# eBox_Power.net
KiCad netlist of a schematic drawn in Altium Designer
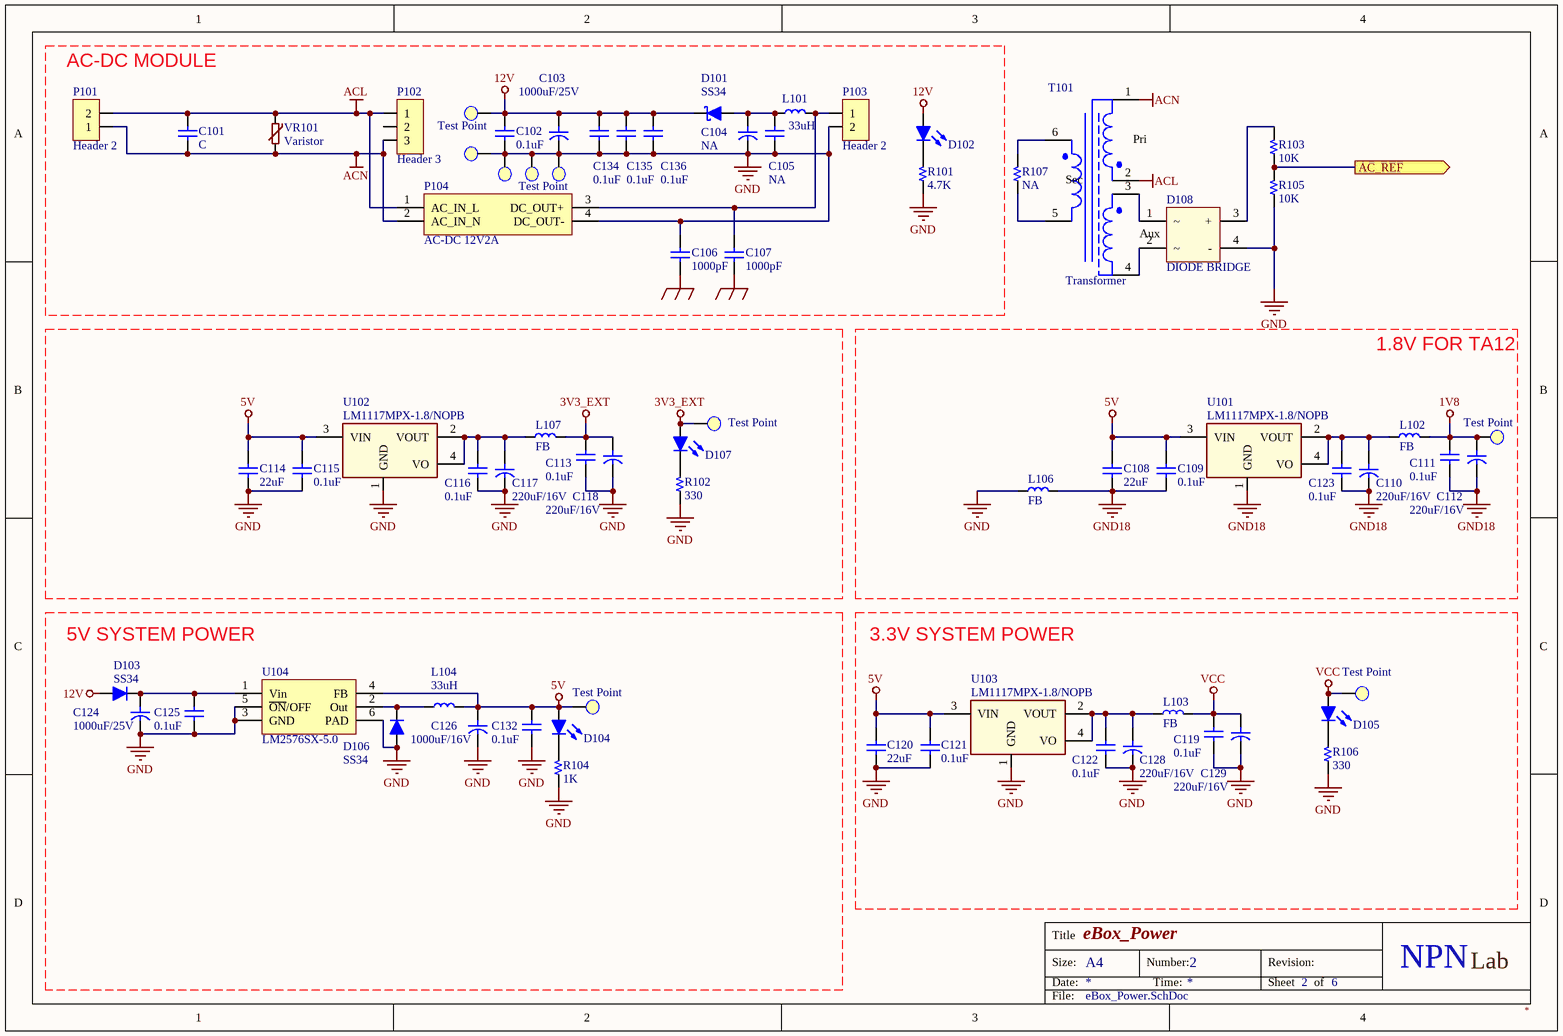
[diagram p0: eBox_Power.SchDoc]

(export (version "E")
  (design (tool "Eeschema 10.0.6"))
  (components
    (comp (ref "1V8")
      (value "Test Point")
      (footprint "TestPoint/SMD/1.5mm")
      (libsource (lib "chipfc_altium_libs_extras") (part "Test Point"))
    )
    (comp (ref "3V3")
      (value "Test Point")
      (footprint "TestPoint/SMD/1.5mm")
      (libsource (lib "chipfc_altium_libs_extras") (part "Test Point"))
    )
    (comp (ref "5V")
      (value "Test Point")
      (footprint "TestPoint/SMD/1.5mm")
      (libsource (lib "chipfc_altium_libs_extras") (part "Test Point"))
    )
    (comp (ref "12V")
      (value "Test Point")
      (footprint "TestPoint/SMD/1.5mm")
      (libsource (lib "chipfc_altium_libs_extras") (part "Test Point"))
    )
    (comp (ref "C101")
      (value "C")
      (footprint "CAP Ceramic/D7.0/F7.5")
      (description "Capacitor non-pol")
      (libsource (lib "chipfc_altium_libs") (part "Capacitor NP"))
    )
    (comp (ref "C102")
      (value "0.1uF")
      (footprint "C 0805")
      (description "CAP CER 0.1UF 50V X7R 0603")
      (libsource (lib "chipfc_altium_libs") (part "Capacitor NP"))
    )
    (comp (ref "C103")
      (value "1000uF/25V")
      (footprint "CAP/D100/H200/LS50")
      (description "Capacitor pol")
      (libsource (lib "") (part "Capacitor_1"))
    )
    (comp (ref "C104")
      (value "NA")
      (footprint "CAP/D100/H200/LS50")
      (description "Capacitor pol")
      (libsource (lib "") (part "Capacitor_1"))
    )
    (comp (ref "C105")
      (value "NA")
      (footprint "C 0805")
      (description "CAP CER 0.1UF 50V X7R 0805")
      (libsource (lib "chipfc_altium_libs") (part "Capacitor NP"))
    )
    (comp (ref "C106")
      (value "1000pF")
      (footprint "CAP Ceramic/W300")
      (description "Capacitor non-pol")
      (libsource (lib "chipfc_altium_libs") (part "Capacitor NP"))
    )
    (comp (ref "C107")
      (value "1000pF")
      (footprint "CAP Ceramic/W300")
      (description "Capacitor non-pol")
      (libsource (lib "chipfc_altium_libs") (part "Capacitor NP"))
    )
    (comp (ref "C108")
      (value "22uF")
      (footprint "C 1210")
      (description "CAP CER 22UF 50V X7R 1210")
      (libsource (lib "chipfc_altium_libs") (part "Capacitor NP"))
    )
    (comp (ref "C109")
      (value "0.1uF")
      (footprint "C 0805")
      (description "CAP CER 0.1UF 50V X7R 0603")
      (libsource (lib "chipfc_altium_libs") (part "Capacitor NP"))
    )
    (comp (ref "C110")
      (value "220uF/16V")
      (footprint "CYL/D.250/LS.100")
      (description "CAP TANT 100UF 20% 16V 2917")
      (libsource (lib "chipfc_altium_libs") (part "Capacitor"))
    )
    (comp (ref "C111")
      (value "0.1uF")
      (footprint "C 0805")
      (description "CAP CER 0.1UF 50V X7R 0603")
      (libsource (lib "chipfc_altium_libs") (part "Capacitor NP"))
    )
    (comp (ref "C112")
      (value "220uF/16V")
      (footprint "CYL/D.250/LS.100")
      (description "CAP TANT 100UF 20% 16V 2917")
      (libsource (lib "chipfc_altium_libs") (part "Capacitor"))
    )
    (comp (ref "C113")
      (value "0.1uF")
      (footprint "C 0805")
      (description "CAP CER 0.1UF 50V X7R 0603")
      (libsource (lib "chipfc_altium_libs") (part "Capacitor NP"))
    )
    (comp (ref "C114")
      (value "22uF")
      (footprint "C 1210")
      (description "CAP CER 22UF 50V X7R 1210")
      (libsource (lib "chipfc_altium_libs") (part "Capacitor NP"))
    )
    (comp (ref "C115")
      (value "0.1uF")
      (footprint "C 0805")
      (description "CAP CER 0.1UF 50V X7R 0603")
      (libsource (lib "chipfc_altium_libs") (part "Capacitor NP"))
    )
    (comp (ref "C116")
      (value "0.1uF")
      (footprint "C 0805")
      (description "CAP CER 0.1UF 50V X7R 0603")
      (libsource (lib "chipfc_altium_libs") (part "Capacitor NP"))
    )
    (comp (ref "C117")
      (value "220uF/16V")
      (footprint "CYL/D.250/LS.100")
      (description "CAP TANT 100UF 20% 16V 2917")
      (libsource (lib "chipfc_altium_libs") (part "Capacitor"))
    )
    (comp (ref "C118")
      (value "220uF/16V")
      (footprint "CYL/D.250/LS.100")
      (description "CAP TANT 100UF 20% 16V 2917")
      (libsource (lib "chipfc_altium_libs") (part "Capacitor"))
    )
    (comp (ref "C119")
      (value "0.1uF")
      (footprint "C 0805")
      (description "CAP CER 0.1UF 50V X7R 0603")
      (libsource (lib "chipfc_altium_libs") (part "Capacitor NP"))
    )
    (comp (ref "C120")
      (value "22uF")
      (footprint "C 1210")
      (description "CAP CER 22UF 50V X7R 1210")
      (libsource (lib "chipfc_altium_libs") (part "Capacitor NP"))
    )
    (comp (ref "C121")
      (value "0.1uF")
      (footprint "C 0805")
      (description "CAP CER 0.1UF 50V X7R 0603")
      (libsource (lib "chipfc_altium_libs") (part "Capacitor NP"))
    )
    (comp (ref "C122")
      (value "0.1uF")
      (footprint "C 0805")
      (description "CAP CER 0.1UF 50V X7R 0603")
      (libsource (lib "chipfc_altium_libs") (part "Capacitor NP"))
    )
    (comp (ref "C123")
      (value "0.1uF")
      (footprint "C 0805")
      (description "CAP CER 0.1UF 50V X7R 0603")
      (libsource (lib "chipfc_altium_libs") (part "Capacitor NP"))
    )
    (comp (ref "C124")
      (value "1000uF/25V")
      (footprint "CAP/D100/H200/LS50")
      (description "Capacitor pol")
      (libsource (lib "") (part "Capacitor_1"))
    )
    (comp (ref "C125")
      (value "0.1uF")
      (footprint "C 0805")
      (description "CAP CER 0.1UF 50V X7R 0805")
      (libsource (lib "chipfc_altium_libs") (part "Capacitor NP"))
    )
    (comp (ref "C126")
      (value "1000uF/16V")
      (footprint "CAP/D100/H200/LS50")
      (description "Capacitor pol")
      (libsource (lib "") (part "Capacitor_1"))
    )
    (comp (ref "C128")
      (value "220uF/16V")
      (footprint "CYL/D.250/LS.100")
      (description "CAP TANT 100UF 20% 16V 2917")
      (libsource (lib "chipfc_altium_libs") (part "Capacitor"))
    )
    (comp (ref "C129")
      (value "220uF/16V")
      (footprint "CYL/D.250/LS.100")
      (description "CAP TANT 100UF 20% 16V 2917")
      (libsource (lib "chipfc_altium_libs") (part "Capacitor"))
    )
    (comp (ref "C132")
      (value "0.1uF")
      (footprint "C 0805")
      (description "CAP CER 0.1UF 50V X7R 0805")
      (libsource (lib "chipfc_altium_libs") (part "Capacitor NP"))
    )
    (comp (ref "C134")
      (value "0.1uF")
      (footprint "C 0805")
      (description "CAP CER 0.1UF 50V X7R 0805")
      (libsource (lib "chipfc_altium_libs") (part "Capacitor NP"))
    )
    (comp (ref "C135")
      (value "0.1uF")
      (footprint "C 0805")
      (description "CAP CER 0.1UF 50V X7R 0805")
      (libsource (lib "chipfc_altium_libs") (part "Capacitor NP"))
    )
    (comp (ref "C136")
      (value "0.1uF")
      (footprint "C 0805")
      (description "CAP CER 0.1UF 50V X7R 0805")
      (libsource (lib "chipfc_altium_libs") (part "Capacitor NP"))
    )
    (comp (ref "D101")
      (value "SS34")
      (footprint "DO-214AB (SMC)")
      (description "DIODE SCHOTTKY 40V 3A SUB SMA")
      (libsource (lib "chipfc_altium_libs") (part "Diode Schottky"))
    )
    (comp (ref "D102")
      (value "5V Led")
      (footprint "LED 3MM - red")
      (description "LED RED CLEAR 0603 SMD")
      (libsource (lib "chipfc_altium_libs") (part "Led"))
    )
    (comp (ref "D103")
      (value "SS34")
      (footprint "DO-214AC (SMA) L")
      (description "Default Diode")
      (libsource (lib "chipfc_altium_libs") (part "Diode"))
    )
    (comp (ref "D104")
      (value "5V Led")
      (footprint "LED 3MM - red")
      (description "LED RED CLEAR 0603 SMD")
      (libsource (lib "chipfc_altium_libs") (part "Led"))
    )
    (comp (ref "D105")
      (value "5V Led")
      (footprint "LED 3MM - red")
      (description "LED RED CLEAR 0603 SMD")
      (libsource (lib "chipfc_altium_libs") (part "Led"))
    )
    (comp (ref "D106")
      (value "SS34")
      (footprint "DO-214AC (SMA) L")
      (description "Default Diode")
      (libsource (lib "chipfc_altium_libs") (part "Diode"))
    )
    (comp (ref "D107")
      (value "5V Led")
      (footprint "LED 3MM - red")
      (description "LED RED CLEAR 0603 SMD")
      (libsource (lib "chipfc_altium_libs") (part "Led"))
    )
    (comp (ref "D108")
      (value "DIODE BRIDGE")
      (footprint "DiodeBridge-SOIC4")
      (description "Diode bridge")
      (libsource (lib "chipfc_altium_libs") (part "DIODE BRIDGE"))
    )
    (comp (ref "GND1")
      (value "Test Point")
      (footprint "TESTPOINT/1/Black")
      (libsource (lib "chipfc_altium_libs_extras") (part "Test Point"))
    )
    (comp (ref "GND2")
      (value "Test Point")
      (footprint "TESTPOINT/1/Black")
      (libsource (lib "chipfc_altium_libs_extras") (part "Test Point"))
    )
    (comp (ref "GND3")
      (value "Test Point")
      (footprint "TESTPOINT/1/Black")
      (libsource (lib "chipfc_altium_libs_extras") (part "Test Point"))
    )
    (comp (ref "GND4")
      (value "Test Point")
      (footprint "TESTPOINT/1/Black")
      (libsource (lib "chipfc_altium_libs_extras") (part "Test Point"))
    )
    (comp (ref "L101")
      (value "33uH")
      (footprint "Inductor SMD 6.5x6.5x3.0")
      (description "FIXED IND 2.2UH 3A 105 MOHM SMD")
      (fields (field (name "PART NO") "MHCI06030-2R2M-R8"))
      (libsource (lib "chipfc_altium_libs") (part "Inductor"))
    )
    (comp (ref "L102")
      (value "FB")
      (footprint "L 0805 (2012)")
      (libsource (lib "chipfc_altium_libs") (part "Inductor"))
    )
    (comp (ref "L103")
      (value "FB")
      (footprint "L 0805 (2012)")
      (libsource (lib "chipfc_altium_libs") (part "Inductor"))
    )
    (comp (ref "L104")
      (value "33uH")
      (footprint "Inductor SMD 12x12x8")
      (description "Inductor")
      (libsource (lib "chipfc_altium_libs") (part "Inductor"))
    )
    (comp (ref "L105")
      (value "33uH")
      (footprint "Inductor SMD 12x12x8")
      (description "Inductor")
      (libsource (lib "chipfc_altium_libs") (part "Inductor"))
    )
    (comp (ref "L106")
      (value "FB")
      (footprint "L 0805 (2012)")
      (description "Inductor")
      (libsource (lib "chipfc_altium_libs") (part "Inductor"))
    )
    (comp (ref "L107")
      (value "FB")
      (footprint "L 0805 (2012)")
      (libsource (lib "chipfc_altium_libs") (part "Inductor"))
    )
    (comp (ref "P101")
      (value "Header 2")
      (footprint "HDR/Terminal/2/10mm")
      (description "Header, 2-Pin")
      (libsource (lib "") (part "Header 2_1"))
    )
    (comp (ref "P102")
      (value "Header 3")
      (footprint "HDR/Header/3/VH")
      (description "Header, 3-Pin")
      (libsource (lib "chipfc_altium_libs") (part "Header 3"))
    )
    (comp (ref "P103")
      (value "Header 2")
      (footprint "HDR/Header/2/VH")
      (description "Header, 2-Pin")
      (libsource (lib "chipfc_altium_libs") (part "Header 2"))
    )
    (comp (ref "P104")
      (value "AC-DC 12V2A")
      (footprint "AC-DC 12V2A")
      (description "AC-DC 12V3A")
      (libsource (lib "chipfc_altium_libs") (part "AC-DC 12V3A"))
    )
    (comp (ref "R101")
      (value "4.7K")
      (footprint "R 0603")
      (description "RES SMD 4.7K OHM 1% 1/10W 0603")
      (libsource (lib "chipfc_altium_libs") (part "Resistor"))
    )
    (comp (ref "R102")
      (value "330")
      (footprint "R 0603")
      (description "RES SMD 330 OHM 1% 1/10W 0603")
      (libsource (lib "chipfc_altium_libs") (part "Resistor"))
    )
    (comp (ref "R103")
      (value "10K")
      (footprint "R 0805")
      (description "RES SMD 4.7K OHM 1% 1/10W 0603")
      (libsource (lib "chipfc_altium_libs") (part "Resistor"))
    )
    (comp (ref "R104")
      (value "1K")
      (footprint "R 0603")
      (description "RES SMD 1K OHM 1% 1/10W 0603")
      (libsource (lib "chipfc_altium_libs") (part "Resistor"))
    )
    (comp (ref "R105")
      (value "10K")
      (footprint "R 0805")
      (description "RES SMD 4.7K OHM 1% 1/10W 0603")
      (libsource (lib "chipfc_altium_libs") (part "Resistor"))
    )
    (comp (ref "R106")
      (value "330")
      (footprint "R 0603")
      (description "RES SMD 330 OHM 1% 1/10W 0603")
      (libsource (lib "chipfc_altium_libs") (part "Resistor"))
    )
    (comp (ref "R107")
      (value "NA")
      (footprint "R 0805")
      (description "RES SMD 4.7K OHM 1% 1/10W 0603")
      (libsource (lib "chipfc_altium_libs") (part "Resistor"))
    )
    (comp (ref "T101")
      (value "Transformer")
      (footprint "Trans. EE10/6P/F")
      (description "Transformer 6-PIN")
      (libsource (lib "chipfc_altium_libs") (part "Trans 6-PIN"))
    )
    (comp (ref "U101")
      (value "LM1117MPX-1.8/NOPB")
      (footprint "SOT-223")
      (description "IC REG LINEAR 1.8V 800MA SOT223")
      (libsource (lib "chipfc_altium_libs") (part "AMS1117"))
    )
    (comp (ref "U102")
      (value "LM1117MPX-1.8/NOPB")
      (footprint "SOT-223")
      (description "IC REG LINEAR 1.8V 800MA SOT223")
      (libsource (lib "chipfc_altium_libs") (part "AMS1117"))
    )
    (comp (ref "U103")
      (value "LM1117MPX-1.8/NOPB")
      (footprint "SOT-223")
      (description "IC REG LINEAR 1.8V 800MA SOT223")
      (libsource (lib "chipfc_altium_libs") (part "AMS1117"))
    )
    (comp (ref "U104")
      (value "LM2576SX-5.0")
      (footprint "TO-263-6")
      (description "IC REG BUCK 5V 3A TO263-5")
      (fields (field (name "PART NO") "LM2576SX-5.0/NOPB"))
      (libsource (lib "chipfc_altium_libs") (part "LM2576SX-5.0"))
    )
    (comp (ref "VCC")
      (value "Test Point")
      (footprint "TestPoint/SMD/1.5mm")
      (libsource (lib "chipfc_altium_libs_extras") (part "Test Point"))
    )
    (comp (ref "VR101")
      (value "Varistor")
      (footprint "VARISTOR DISC 5MM/7MM")
      (libsource (lib "chipfc_altium_libs") (part "Varistor"))
    )
  )
  (nets
    (net (code "1") (name "/AC_REF") (class "Default")
      (node (ref "R103") (pin "1") (pinfunction "1_1") (pintype "passive"))
      (node (ref "R105") (pin "2") (pinfunction "2_2") (pintype "passive"))
    )
    (net (code "2") (name "1V8") (class "Default")
      (node (ref "1V8") (pin "1") (pinfunction "TP_1") (pintype "passive"))
      (node (ref "C111") (pin "1") (pinfunction "1_1") (pintype "passive"))
      (node (ref "C112") (pin "1") (pinfunction "1_1") (pintype "passive"))
      (node (ref "L102") (pin "2") (pinfunction "2_2") (pintype "passive"))
    )
    (net (code "3") (name "3V3_EXT") (class "Default")
      (node (ref "3V3") (pin "1") (pinfunction "TP_1") (pintype "passive"))
      (node (ref "C113") (pin "1") (pinfunction "1_1") (pintype "passive"))
      (node (ref "C118") (pin "1") (pinfunction "1_1") (pintype "passive"))
      (node (ref "D107") (pin "1") (pinfunction "A_1") (pintype "passive"))
      (node (ref "L107") (pin "2") (pinfunction "2_2") (pintype "passive"))
    )
    (net (code "4") (name "5V") (class "Default")
      (node (ref "5V") (pin "1") (pinfunction "TP_1") (pintype "passive"))
      (node (ref "C108") (pin "1") (pinfunction "1_1") (pintype "passive"))
      (node (ref "C109") (pin "1") (pinfunction "1_1") (pintype "passive"))
      (node (ref "C114") (pin "1") (pinfunction "1_1") (pintype "passive"))
      (node (ref "C115") (pin "1") (pinfunction "1_1") (pintype "passive"))
      (node (ref "C120") (pin "1") (pinfunction "1_1") (pintype "passive"))
      (node (ref "C121") (pin "1") (pinfunction "1_1") (pintype "passive"))
      (node (ref "C126") (pin "1") (pinfunction "1_1") (pintype "passive"))
      (node (ref "C132") (pin "1") (pinfunction "1_1") (pintype "passive"))
      (node (ref "D104") (pin "1") (pinfunction "A_1") (pintype "passive"))
      (node (ref "L104") (pin "2") (pinfunction "2_2") (pintype "passive"))
      (node (ref "U101") (pin "3") (pinfunction "VIN_3") (pintype "power_in"))
      (node (ref "U102") (pin "3") (pinfunction "VIN_3") (pintype "power_in"))
      (node (ref "U103") (pin "3") (pinfunction "VIN_3") (pintype "power_in"))
      (node (ref "U104") (pin "4") (pinfunction "FB_4") (pintype "passive"))
    )
    (net (code "5") (name "12V") (class "Default")
      (node (ref "12V") (pin "1") (pinfunction "TP_1") (pintype "passive"))
      (node (ref "C102") (pin "1") (pinfunction "1_1") (pintype "passive"))
      (node (ref "C103") (pin "1") (pinfunction "1_1") (pintype "passive"))
      (node (ref "C134") (pin "1") (pinfunction "1_1") (pintype "passive"))
      (node (ref "C135") (pin "1") (pinfunction "1_1") (pintype "passive"))
      (node (ref "C136") (pin "1") (pinfunction "1_1") (pintype "passive"))
      (node (ref "D101") (pin "2") (pinfunction "K_2") (pintype "passive"))
      (node (ref "D102") (pin "1") (pinfunction "A_1") (pintype "passive"))
      (node (ref "D103") (pin "1") (pinfunction "A_1") (pintype "passive"))
    )
    (net (code "6") (name "ACL") (class "Default")
      (node (ref "C101") (pin "1") (pinfunction "1_1") (pintype "passive"))
      (node (ref "P101") (pin "2") (pinfunction "2_2") (pintype "passive"))
      (node (ref "P102") (pin "1") (pinfunction "1_1") (pintype "passive"))
      (node (ref "P104") (pin "1") (pinfunction "AC_IN_L_1") (pintype "passive"))
      (node (ref "T101") (pin "2") (pinfunction "A2_2") (pintype "passive"))
      (node (ref "VR101") (pin "2") (pinfunction "2_2") (pintype "passive"))
    )
    (net (code "7") (name "ACN") (class "Default")
      (node (ref "C101") (pin "2") (pinfunction "2_2") (pintype "passive"))
      (node (ref "P101") (pin "1") (pinfunction "1_1") (pintype "passive"))
      (node (ref "P102") (pin "3") (pinfunction "3_3") (pintype "passive"))
      (node (ref "P104") (pin "2") (pinfunction "AC_IN_N_2") (pintype "passive"))
      (node (ref "T101") (pin "1") (pinfunction "A1_1") (pintype "passive"))
      (node (ref "VR101") (pin "1") (pinfunction "1_1") (pintype "passive"))
    )
    (net (code "8") (name "GND") (class "Default")
      (node (ref "C102") (pin "2") (pinfunction "2_2") (pintype "passive"))
      (node (ref "C103") (pin "2") (pinfunction "2_2") (pintype "passive"))
      (node (ref "C104") (pin "2") (pinfunction "2_2") (pintype "passive"))
      (node (ref "C105") (pin "2") (pinfunction "2_2") (pintype "passive"))
      (node (ref "C106") (pin "1") (pinfunction "1_1") (pintype "passive"))
      (node (ref "C113") (pin "2") (pinfunction "2_2") (pintype "passive"))
      (node (ref "C114") (pin "2") (pinfunction "2_2") (pintype "passive"))
      (node (ref "C115") (pin "2") (pinfunction "2_2") (pintype "passive"))
      (node (ref "C116") (pin "2") (pinfunction "2_2") (pintype "passive"))
      (node (ref "C117") (pin "2") (pinfunction "2_2") (pintype "passive"))
      (node (ref "C118") (pin "2") (pinfunction "2_2") (pintype "passive"))
      (node (ref "C119") (pin "2") (pinfunction "2_2") (pintype "passive"))
      (node (ref "C120") (pin "2") (pinfunction "2_2") (pintype "passive"))
      (node (ref "C121") (pin "2") (pinfunction "2_2") (pintype "passive"))
      (node (ref "C122") (pin "2") (pinfunction "2_2") (pintype "passive"))
      (node (ref "C124") (pin "2") (pinfunction "2_2") (pintype "passive"))
      (node (ref "C125") (pin "2") (pinfunction "2_2") (pintype "passive"))
      (node (ref "C126") (pin "2") (pinfunction "2_2") (pintype "passive"))
      (node (ref "C128") (pin "2") (pinfunction "2_2") (pintype "passive"))
      (node (ref "C129") (pin "2") (pinfunction "2_2") (pintype "passive"))
      (node (ref "C132") (pin "2") (pinfunction "2_2") (pintype "passive"))
      (node (ref "C134") (pin "2") (pinfunction "2_2") (pintype "passive"))
      (node (ref "C135") (pin "2") (pinfunction "2_2") (pintype "passive"))
      (node (ref "C136") (pin "2") (pinfunction "2_2") (pintype "passive"))
      (node (ref "D106") (pin "1") (pinfunction "A_1") (pintype "passive"))
      (node (ref "D108") (pin "4") (pinfunction "-_4") (pintype "passive"))
      (node (ref "GND1") (pin "1") (pinfunction "TP_1") (pintype "passive"))
      (node (ref "GND2") (pin "1") (pinfunction "TP_1") (pintype "passive"))
      (node (ref "GND3") (pin "1") (pinfunction "TP_1") (pintype "passive"))
      (node (ref "GND4") (pin "1") (pinfunction "TP_1") (pintype "passive"))
      (node (ref "L106") (pin "1") (pinfunction "1_1") (pintype "passive"))
      (node (ref "P103") (pin "2") (pinfunction "2_2") (pintype "passive"))
      (node (ref "P104") (pin "4") (pinfunction "DC_OUT-_4") (pintype "passive"))
      (node (ref "R101") (pin "1") (pinfunction "1_1") (pintype "passive"))
      (node (ref "R102") (pin "1") (pinfunction "1_1") (pintype "passive"))
      (node (ref "R104") (pin "1") (pinfunction "1_1") (pintype "passive"))
      (node (ref "R105") (pin "1") (pinfunction "1_1") (pintype "passive"))
      (node (ref "R106") (pin "1") (pinfunction "1_1") (pintype "passive"))
      (node (ref "U102") (pin "1") (pinfunction "GND_1") (pintype "passive"))
      (node (ref "U103") (pin "1") (pinfunction "GND_1") (pintype "passive"))
      (node (ref "U104") (pin "3") (pinfunction "GND_3") (pintype "passive"))
      (node (ref "U104") (pin "5") (pinfunction "~{ON}/OFF_5") (pintype "passive"))
      (node (ref "U104") (pin "6") (pinfunction "PAD_6") (pintype "passive"))
    )
    (net (code "9") (name "GND18") (class "Default")
      (node (ref "C108") (pin "2") (pinfunction "2_2") (pintype "passive"))
      (node (ref "C109") (pin "2") (pinfunction "2_2") (pintype "passive"))
      (node (ref "C110") (pin "2") (pinfunction "2_2") (pintype "passive"))
      (node (ref "C111") (pin "2") (pinfunction "2_2") (pintype "passive"))
      (node (ref "C112") (pin "2") (pinfunction "2_2") (pintype "passive"))
      (node (ref "C123") (pin "2") (pinfunction "2_2") (pintype "passive"))
      (node (ref "L106") (pin "2") (pinfunction "2_2") (pintype "passive"))
      (node (ref "U101") (pin "1") (pinfunction "GND_1") (pintype "passive"))
    )
    (net (code "10") (name "GNDEARTH") (class "Default")
      (node (ref "C106") (pin "2") (pinfunction "2_2") (pintype "passive"))
      (node (ref "C107") (pin "2") (pinfunction "2_2") (pintype "passive"))
    )
    (net (code "11") (name "Net-(D101-A)") (class "Default")
      (node (ref "C104") (pin "1") (pinfunction "1_1") (pintype "passive"))
      (node (ref "C105") (pin "1") (pinfunction "1_1") (pintype "passive"))
      (node (ref "D101") (pin "1") (pinfunction "A_1") (pintype "passive"))
      (node (ref "L101") (pin "1") (pinfunction "1_1") (pintype "passive"))
      (node (ref "L105") (pin "1") (pinfunction "1_1") (pintype "passive"))
    )
    (net (code "12") (name "Net-(D102-K)") (class "Default")
      (node (ref "D102") (pin "2") (pinfunction "K_2") (pintype "passive"))
      (node (ref "R101") (pin "2") (pinfunction "2_2") (pintype "passive"))
    )
    (net (code "13") (name "Net-(D103-K)") (class "Default")
      (node (ref "C124") (pin "1") (pinfunction "1_1") (pintype "passive"))
      (node (ref "C125") (pin "1") (pinfunction "1_1") (pintype "passive"))
      (node (ref "D103") (pin "2") (pinfunction "K_2") (pintype "passive"))
      (node (ref "U104") (pin "1") (pinfunction "Vin_1") (pintype "passive"))
    )
    (net (code "14") (name "Net-(D104-K)") (class "Default")
      (node (ref "D104") (pin "2") (pinfunction "K_2") (pintype "passive"))
      (node (ref "R104") (pin "2") (pinfunction "2_2") (pintype "passive"))
    )
    (net (code "15") (name "Net-(D105-K)") (class "Default")
      (node (ref "D105") (pin "2") (pinfunction "K_2") (pintype "passive"))
      (node (ref "R106") (pin "2") (pinfunction "2_2") (pintype "passive"))
    )
    (net (code "16") (name "Net-(D106-K)") (class "Default")
      (node (ref "D106") (pin "2") (pinfunction "K_2") (pintype "passive"))
      (node (ref "L104") (pin "1") (pinfunction "1_1") (pintype "passive"))
      (node (ref "U104") (pin "2") (pinfunction "Out_2") (pintype "passive"))
    )
    (net (code "17") (name "Net-(D107-K)") (class "Default")
      (node (ref "D107") (pin "2") (pinfunction "K_2") (pintype "passive"))
      (node (ref "R102") (pin "2") (pinfunction "2_2") (pintype "passive"))
    )
    (net (code "18") (name "Net-(D108-+)") (class "Default")
      (node (ref "D108") (pin "3") (pinfunction "+_3") (pintype "passive"))
      (node (ref "R103") (pin "2") (pinfunction "2_2") (pintype "passive"))
    )
    (net (code "19") (name "Net-(P104-DC_OUT+)") (class "Default")
      (node (ref "C107") (pin "1") (pinfunction "1_1") (pintype "passive"))
      (node (ref "L101") (pin "2") (pinfunction "2_2") (pintype "passive"))
      (node (ref "L105") (pin "2") (pinfunction "2_2") (pintype "passive"))
      (node (ref "P103") (pin "1") (pinfunction "1_1") (pintype "passive"))
      (node (ref "P104") (pin "3") (pinfunction "DC_OUT+_3") (pintype "passive"))
    )
    (net (code "20") (name "Net-(T101-B1)") (class "Default")
      (node (ref "D108") (pin "1") (pinfunction "~_1") (pintype "passive"))
      (node (ref "T101") (pin "3") (pinfunction "B1_3") (pintype "passive"))
    )
    (net (code "21") (name "Net-(T101-B2)") (class "Default")
      (node (ref "D108") (pin "2") (pinfunction "~_2") (pintype "passive"))
      (node (ref "T101") (pin "4") (pinfunction "B2_4") (pintype "passive"))
    )
    (net (code "22") (name "Net-(T101-C1)") (class "Default")
      (node (ref "R107") (pin "2") (pinfunction "2_2") (pintype "passive"))
      (node (ref "T101") (pin "6") (pinfunction "C1_6") (pintype "passive"))
    )
    (net (code "23") (name "Net-(T101-C2)") (class "Default")
      (node (ref "R107") (pin "1") (pinfunction "1_1") (pintype "passive"))
      (node (ref "T101") (pin "5") (pinfunction "C2_5") (pintype "passive"))
    )
    (net (code "24") (name "Net-(U101-VO)") (class "Default")
      (node (ref "C110") (pin "1") (pinfunction "1_1") (pintype "passive"))
      (node (ref "C123") (pin "1") (pinfunction "1_1") (pintype "passive"))
      (node (ref "L102") (pin "1") (pinfunction "1_1") (pintype "passive"))
      (node (ref "U101") (pin "2") (pinfunction "VOUT_2") (pintype "passive"))
      (node (ref "U101") (pin "4") (pinfunction "VO_4") (pintype "passive"))
    )
    (net (code "25") (name "Net-(U102-VO)") (class "Default")
      (node (ref "C116") (pin "1") (pinfunction "1_1") (pintype "passive"))
      (node (ref "C117") (pin "1") (pinfunction "1_1") (pintype "passive"))
      (node (ref "L107") (pin "1") (pinfunction "1_1") (pintype "passive"))
      (node (ref "U102") (pin "2") (pinfunction "VOUT_2") (pintype "passive"))
      (node (ref "U102") (pin "4") (pinfunction "VO_4") (pintype "passive"))
    )
    (net (code "26") (name "Net-(U103-VO)") (class "Default")
      (node (ref "C122") (pin "1") (pinfunction "1_1") (pintype "passive"))
      (node (ref "C128") (pin "1") (pinfunction "1_1") (pintype "passive"))
      (node (ref "L103") (pin "1") (pinfunction "1_1") (pintype "passive"))
      (node (ref "U103") (pin "2") (pinfunction "VOUT_2") (pintype "passive"))
      (node (ref "U103") (pin "4") (pinfunction "VO_4") (pintype "passive"))
    )
    (net (code "27") (name "VCC") (class "Default")
      (node (ref "C119") (pin "1") (pinfunction "1_1") (pintype "passive"))
      (node (ref "C129") (pin "1") (pinfunction "1_1") (pintype "passive"))
      (node (ref "D105") (pin "1") (pinfunction "A_1") (pintype "passive"))
      (node (ref "L103") (pin "2") (pinfunction "2_2") (pintype "passive"))
      (node (ref "VCC") (pin "1") (pinfunction "TP_1") (pintype "passive"))
    )
    (net (code "28") (name "unconnected-(P102-Pad2)") (class "Default")
      (node (ref "P102") (pin "2") (pinfunction "2_2") (pintype "passive"))
    )
  )
)
